# Smart_Agriculture_Schematic.net
KiCad netlist of a schematic drawn in Altium Designer
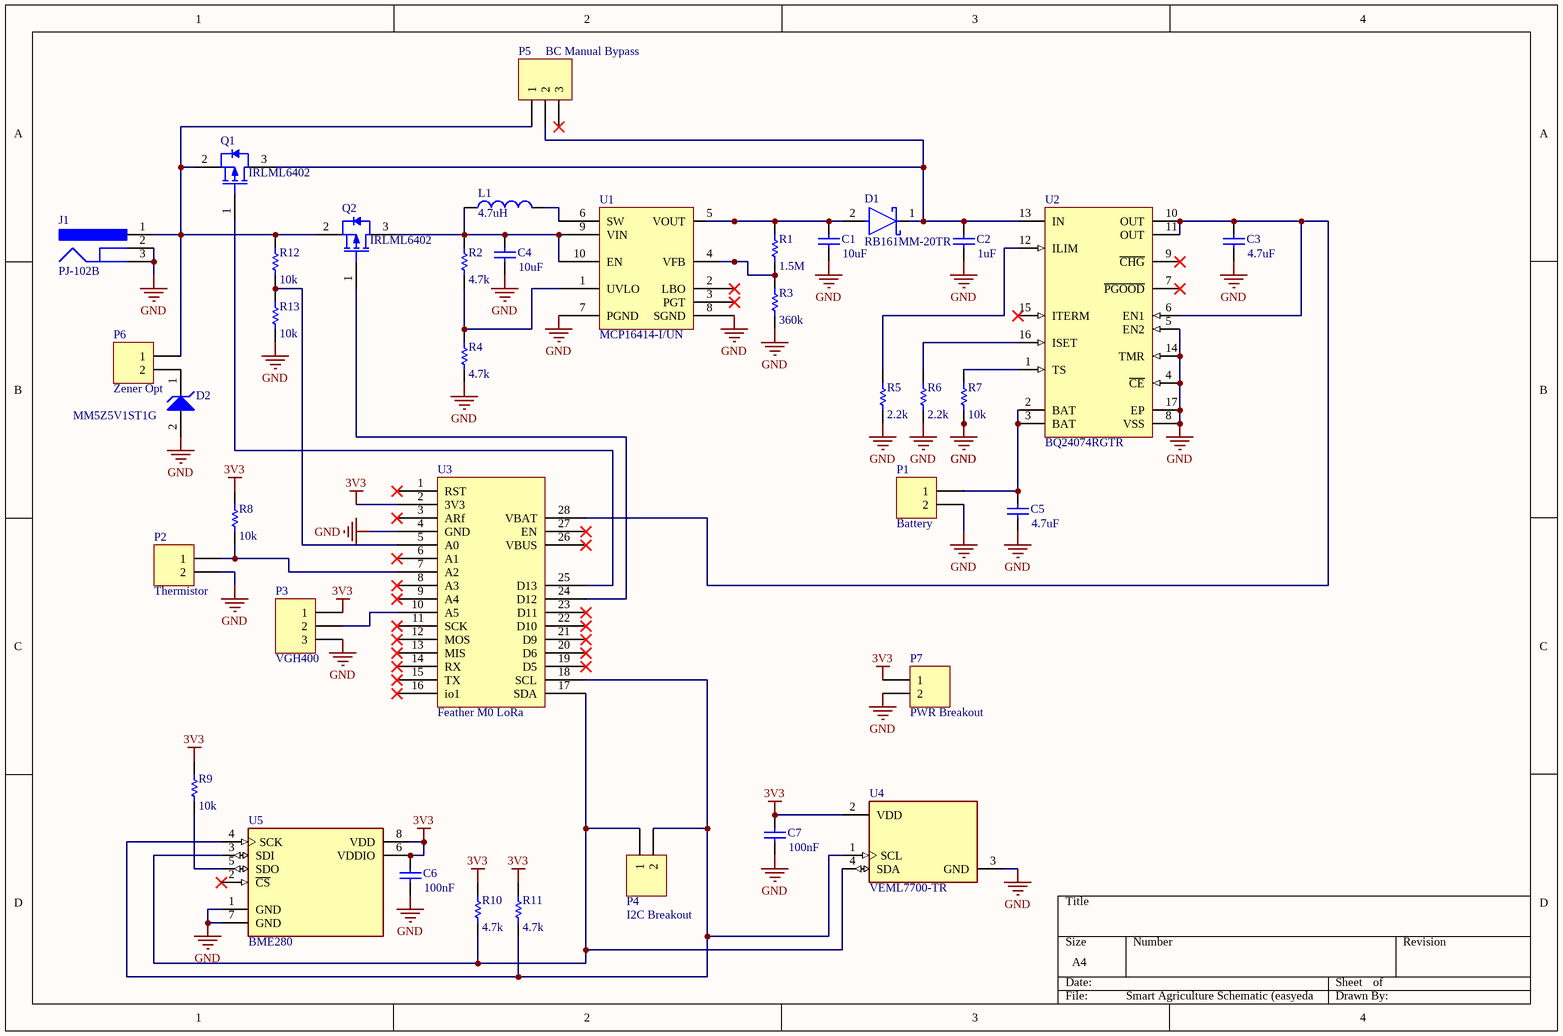
[diagram p0: Smart Agriculture Schematic (easyeda backup).SchDoc]

(export (version "E")
  (design (tool "Eeschema 10.0.6"))
  (components
    (comp (ref "C1")
      (value "10uF")
      (footprint "1608[0603]")
      (description "Capacitor")
      (fields (field (name "PUBLISHER") "Altium Limited"))
      (libsource (lib "Miscellaneous Devices") (part "Cap"))
    )
    (comp (ref "C2")
      (value "1uF")
      (footprint "1608[0603]")
      (description "Capacitor")
      (fields (field (name "PUBLISHER") "Altium Limited"))
      (libsource (lib "Miscellaneous Devices") (part "Cap"))
    )
    (comp (ref "C3")
      (value "4.7uF")
      (footprint "1608[0603]")
      (description "Capacitor")
      (fields (field (name "PUBLISHER") "Altium Limited"))
      (libsource (lib "Miscellaneous Devices") (part "Cap"))
    )
    (comp (ref "C4")
      (value "10uF")
      (footprint "1608[0603]")
      (description "Capacitor")
      (fields (field (name "PUBLISHER") "Altium Limited"))
      (libsource (lib "Miscellaneous Devices") (part "Cap"))
    )
    (comp (ref "C5")
      (value "4.7uF")
      (footprint "1608[0603]")
      (description "Capacitor")
      (fields (field (name "PUBLISHER") "Altium Limited"))
      (libsource (lib "Miscellaneous Devices") (part "Cap"))
    )
    (comp (ref "C6")
      (value "100nF")
      (footprint "1608[0603]")
      (description "Capacitor")
      (fields (field (name "PUBLISHER") "Altium Limited"))
      (libsource (lib "Miscellaneous Devices") (part "Cap"))
    )
    (comp (ref "C7")
      (value "100nF")
      (footprint "1608[0603]")
      (description "Capacitor")
      (fields (field (name "PUBLISHER") "Altium Limited"))
      (libsource (lib "Miscellaneous Devices") (part "Cap"))
    )
    (comp (ref "D1")
      (value "RB161MM-20TR")
      (footprint "FP-PMDU-MFG")
      (description "DIODE SCHOTTKY 25V 1A PMDU")
      (fields
        (field (name "MANUFACTURER") "Rohm")
        (field (name "OCTOPART") "https://octopart.com/rb161mm-20tr-rohm-50255147")
      )
      (libsource (lib "Altium Content Vault") (part "1d6ec82d83fb6aee721767c19dac4b9"))
    )
    (comp (ref "D2")
      (value "MM5Z5V1ST1G")
      (footprint "ONSC-SOD-523-2-502-01_V")
      (description "Zener Voltage Regulator, 500 mW, 2-Pin SOD-523, Pb-Free, Tape and Reel")
      (fields (field (name "MANUFACTURER") "On Semiconductor"))
      (libsource (lib "Altium Content Vault") (part "ONSC-K1A2-2"))
    )
    (comp (ref "J1")
      (value "PJ-102B")
      (footprint "CUI-PJ-102B_V")
      (fields (field (name "MANUFACTURER") "CUIInc."))
      (libsource (lib "Altium Content Vault") (part "JACK-2CD3-RN"))
    )
    (comp (ref "L1")
      (value "4.7uH")
      (footprint "1812")
      (description "Inductor")
      (fields (field (name "PUBLISHER") "Altium Limited"))
      (libsource (lib "Miscellaneous Devices") (part "Inductor"))
    )
    (comp (ref "P1")
      (value "Battery")
      (footprint "HDR1X2")
      (description "Header, 2-Pin")
      (fields (field (name "PUBLISHER") "Altium Limited"))
      (libsource (lib "") (part "Header 2_2"))
    )
    (comp (ref "P2")
      (value "Thermistor")
      (footprint "HDR1X2")
      (description "Header, 2-Pin")
      (fields (field (name "PUBLISHER") "Altium Limited"))
      (libsource (lib "") (part "Header 2_2"))
    )
    (comp (ref "P3")
      (value "VGH400")
      (footprint "HDR1X3")
      (description "Header, 3-Pin")
      (fields (field (name "PUBLISHER") "Altium Limited"))
      (libsource (lib "") (part "Header 3_1"))
    )
    (comp (ref "P4")
      (value "I2C Breakout")
      (footprint "HDR1X2")
      (description "Header, 2-Pin")
      (fields (field (name "PUBLISHER") "Altium Limited"))
      (libsource (lib "") (part "Header 2_1"))
    )
    (comp (ref "P5")
      (value "BC Manual Bypass")
      (footprint "HDR1X3")
      (description "Header, 3-Pin")
      (fields (field (name "PUBLISHER") "Altium Limited"))
      (libsource (lib "Miscellaneous Connectors") (part "Header 3"))
    )
    (comp (ref "P6")
      (value "Zener Opt")
      (footprint "HDR1X2")
      (description "Header, 2-Pin")
      (fields (field (name "PUBLISHER") "Altium Limited"))
      (libsource (lib "") (part "Header 2_2"))
    )
    (comp (ref "P7")
      (value "PWR Breakout")
      (footprint "HDR1X2")
      (description "Header, 2-Pin")
      (fields (field (name "PUBLISHER") "Altium Limited"))
      (libsource (lib "Miscellaneous Connectors") (part "Header 2"))
    )
    (comp (ref "Q1")
      (value "IRLML6402")
      (footprint "INTR-SOT-23-3_V")
      (fields (field (name "MANUFACTURER") "International Rectifier"))
      (libsource (lib "Altium Content Vault") (part "PEMOS-GSD-3"))
    )
    (comp (ref "Q2")
      (value "IRLML6402")
      (footprint "INTR-SOT-23-3_V")
      (fields (field (name "MANUFACTURER") "International Rectifier"))
      (libsource (lib "Altium Content Vault") (part "PEMOS-GSD-3"))
    )
    (comp (ref "R1")
      (value "1.5M")
      (footprint "1608[0603]")
      (description "Resistor")
      (fields (field (name "PUBLISHER") "Altium Limited"))
      (libsource (lib "Miscellaneous Devices") (part "Res1"))
    )
    (comp (ref "R2")
      (value "4.7k")
      (footprint "1608[0603]")
      (description "Resistor")
      (fields (field (name "PUBLISHER") "Altium Limited"))
      (libsource (lib "Miscellaneous Devices") (part "Res1"))
    )
    (comp (ref "R3")
      (value "360k")
      (footprint "1608[0603]")
      (description "Resistor")
      (fields (field (name "PUBLISHER") "Altium Limited"))
      (libsource (lib "Miscellaneous Devices") (part "Res1"))
    )
    (comp (ref "R4")
      (value "4.7k")
      (footprint "1608[0603]")
      (description "Resistor")
      (fields (field (name "PUBLISHER") "Altium Limited"))
      (libsource (lib "Miscellaneous Devices") (part "Res1"))
    )
    (comp (ref "R5")
      (value "2.2k")
      (footprint "1608[0603]")
      (description "Resistor")
      (fields (field (name "PUBLISHER") "Altium Limited"))
      (libsource (lib "Miscellaneous Devices") (part "Res1"))
    )
    (comp (ref "R6")
      (value "2.2k")
      (footprint "1608[0603]")
      (description "Resistor")
      (fields (field (name "PUBLISHER") "Altium Limited"))
      (libsource (lib "Miscellaneous Devices") (part "Res1"))
    )
    (comp (ref "R7")
      (value "10k")
      (footprint "1608[0603]")
      (description "Resistor")
      (fields (field (name "PUBLISHER") "Altium Limited"))
      (libsource (lib "Miscellaneous Devices") (part "Res1"))
    )
    (comp (ref "R8")
      (value "10k")
      (footprint "1608[0603]")
      (description "Resistor")
      (fields (field (name "PUBLISHER") "Altium Limited"))
      (libsource (lib "Miscellaneous Devices") (part "Res1"))
    )
    (comp (ref "R9")
      (value "10k")
      (footprint "1608[0603]")
      (description "Resistor")
      (fields (field (name "PUBLISHER") "Altium Limited"))
      (libsource (lib "Miscellaneous Devices") (part "Res1"))
    )
    (comp (ref "R10")
      (value "4.7k")
      (footprint "1608[0603]")
      (description "Resistor")
      (fields (field (name "PUBLISHER") "Altium Limited"))
      (libsource (lib "Miscellaneous Devices") (part "Res1"))
    )
    (comp (ref "R11")
      (value "4.7k")
      (footprint "1608[0603]")
      (description "Resistor")
      (fields (field (name "PUBLISHER") "Altium Limited"))
      (libsource (lib "Miscellaneous Devices") (part "Res1"))
    )
    (comp (ref "R12")
      (value "10k")
      (footprint "1608[0603]")
      (description "Resistor")
      (fields (field (name "Comment") "Res1") (field (name "PUBLISHER") "Altium Limited"))
      (libsource (lib "Miscellaneous Devices") (part "Res1"))
    )
    (comp (ref "R13")
      (value "10k")
      (footprint "1608[0603]")
      (description "Resistor")
      (fields (field (name "Comment") "Res1") (field (name "PUBLISHER") "Altium Limited"))
      (libsource (lib "Miscellaneous Devices") (part "Res1"))
    )
    (comp (ref "U1")
      (value "MCP16414-I/UN")
      (footprint "MSOP10_UN_MCH")
      (libsource (lib "MCP16414-IUN") (part "Component_1"))
    )
    (comp (ref "U2")
      (value "BQ24074RGTR")
      (footprint "RGT0016C_V")
      (fields (field (name "MANUFACTURER") "Texas Instruments"))
      (libsource (lib "Altium Content Vault") (part "TI-BQ24074RGT16-1700X1700TP"))
    )
    (comp (ref "U3")
      (value "Feather M0 LoRa")
      (footprint "FeatherM0LoRa")
      (libsource (lib "FeatherM0LoRa") (part "Feather M0 LoRa"))
    )
    (comp (ref "U4")
      (value "VEML7700-TR")
      (footprint "FP-6_550-5300_02-4-MFG")
      (description "SENSOR OPT 545NM AMBIENT 4SMD")
      (fields
        (field (name "OCTOPART") "https://octopart.com/veml7700-tr-vishay-70519713")
        (field (name "MANUFACTURER") "Vishay")
      )
      (libsource (lib "Altium Content Vault") (part "910e2da346148eee15a6bcb182505dc"))
    )
    (comp (ref "U5")
      (value "BME280")
      (footprint "FP-BME280-MFG")
      (description "SENSOR PRESSURE HUMIDITY TEMP")
      (libsource (lib "Altium Content Vault") (part "d58e2f6669bc67e6a2bc6a28610ca79"))
    )
  )
  (nets
    (net (code "1") (name "3V3") (class "Default")
      (node (ref "C6") (pin "2") (pinfunction "2_2") (pintype "passive"))
      (node (ref "C7") (pin "2") (pinfunction "2_2") (pintype "passive"))
      (node (ref "P3") (pin "1") (pinfunction "1_1") (pintype "passive"))
      (node (ref "P7") (pin "1") (pinfunction "1_1") (pintype "passive"))
      (node (ref "R10") (pin "2") (pinfunction "2_2") (pintype "passive"))
      (node (ref "R11") (pin "2") (pinfunction "2_2") (pintype "passive"))
      (node (ref "R8") (pin "2") (pinfunction "2_2") (pintype "passive"))
      (node (ref "R9") (pin "2") (pinfunction "2_2") (pintype "passive"))
      (node (ref "U3") (pin "2") (pinfunction "3V3_2") (pintype "passive"))
      (node (ref "U4") (pin "2") (pinfunction "VDD_2") (pintype "power_in"))
      (node (ref "U5") (pin "6") (pinfunction "VDDIO_6") (pintype "power_in"))
      (node (ref "U5") (pin "8") (pinfunction "VDD_8") (pintype "power_in"))
    )
    (net (code "2") (name "GND") (class "Default")
      (node (ref "C1") (pin "1") (pinfunction "1_1") (pintype "passive"))
      (node (ref "C2") (pin "1") (pinfunction "1_1") (pintype "passive"))
      (node (ref "C3") (pin "1") (pinfunction "1_1") (pintype "passive"))
      (node (ref "C4") (pin "1") (pinfunction "1_1") (pintype "passive"))
      (node (ref "C5") (pin "1") (pinfunction "1_1") (pintype "passive"))
      (node (ref "C6") (pin "1") (pinfunction "1_1") (pintype "passive"))
      (node (ref "C7") (pin "1") (pinfunction "1_1") (pintype "passive"))
      (node (ref "D2") (pin "2") (pinfunction "A_2") (pintype "passive"))
      (node (ref "J1") (pin "2") (pinfunction "2_2") (pintype "passive"))
      (node (ref "J1") (pin "3") (pinfunction "3_3") (pintype "passive"))
      (node (ref "P1") (pin "2") (pinfunction "2_2") (pintype "passive"))
      (node (ref "P2") (pin "2") (pinfunction "2_2") (pintype "passive"))
      (node (ref "P3") (pin "3") (pinfunction "3_3") (pintype "passive"))
      (node (ref "P7") (pin "2") (pinfunction "2_2") (pintype "passive"))
      (node (ref "R13") (pin "1") (pinfunction "1_1") (pintype "passive"))
      (node (ref "R3") (pin "1") (pinfunction "1_1") (pintype "passive"))
      (node (ref "R4") (pin "1") (pinfunction "1_1") (pintype "passive"))
      (node (ref "R5") (pin "1") (pinfunction "1_1") (pintype "passive"))
      (node (ref "R6") (pin "1") (pinfunction "1_1") (pintype "passive"))
      (node (ref "R7") (pin "1") (pinfunction "1_1") (pintype "passive"))
      (node (ref "U1") (pin "7") (pinfunction "PGND_7") (pintype "passive"))
      (node (ref "U1") (pin "8") (pinfunction "SGND_8") (pintype "passive"))
      (node (ref "U2") (pin "14") (pinfunction "TMR_14") (pintype "input"))
      (node (ref "U2") (pin "17") (pinfunction "EP_17") (pintype "power_in"))
      (node (ref "U2") (pin "4") (pinfunction "~{CE}_4") (pintype "input"))
      (node (ref "U2") (pin "5") (pinfunction "EN2_5") (pintype "input"))
      (node (ref "U2") (pin "8") (pinfunction "VSS_8") (pintype "power_in"))
      (node (ref "U3") (pin "4") (pinfunction "GND_4") (pintype "passive"))
      (node (ref "U4") (pin "3") (pinfunction "GND_3") (pintype "power_in"))
      (node (ref "U5") (pin "1") (pinfunction "GND_1") (pintype "power_in"))
      (node (ref "U5") (pin "7") (pinfunction "GND_7") (pintype "power_in"))
    )
    (net (code "3") (name "Net-(C5-Pad2)") (class "Default")
      (node (ref "C5") (pin "2") (pinfunction "2_2") (pintype "passive"))
      (node (ref "P1") (pin "1") (pinfunction "1_1") (pintype "passive"))
      (node (ref "U2") (pin "2") (pinfunction "BAT_2") (pintype "power_in"))
      (node (ref "U2") (pin "3") (pinfunction "BAT_3") (pintype "power_in"))
    )
    (net (code "4") (name "Net-(D1-A)") (class "Default")
      (node (ref "C1") (pin "2") (pinfunction "2_2") (pintype "passive"))
      (node (ref "D1") (pin "2") (pinfunction "A_2") (pintype "passive"))
      (node (ref "R1") (pin "2") (pinfunction "2_2") (pintype "passive"))
      (node (ref "U1") (pin "5") (pinfunction "VOUT_5") (pintype "passive"))
    )
    (net (code "5") (name "Net-(D1-C)") (class "Default")
      (node (ref "C2") (pin "2") (pinfunction "2_2") (pintype "passive"))
      (node (ref "D1") (pin "1") (pinfunction "C_1") (pintype "passive"))
      (node (ref "P5") (pin "2") (pinfunction "2_2") (pintype "passive"))
      (node (ref "Q1") (pin "3") (pinfunction "DRAIN_3") (pintype "passive"))
      (node (ref "U2") (pin "13") (pinfunction "IN_13") (pintype "power_in"))
    )
    (net (code "6") (name "Net-(D2-K)") (class "Default")
      (node (ref "D2") (pin "1") (pinfunction "K_1") (pintype "passive"))
      (node (ref "P6") (pin "2") (pinfunction "2_2") (pintype "passive"))
    )
    (net (code "7") (name "Net-(Q1-GATE)") (class "Default")
      (node (ref "Q1") (pin "1") (pinfunction "GATE_1") (pintype "passive"))
      (node (ref "U3") (pin "25") (pinfunction "D13_25") (pintype "passive"))
    )
    (net (code "8") (name "Net-(Q1-SOURCE)") (class "Default")
      (node (ref "J1") (pin "1") (pinfunction "1_1") (pintype "passive"))
      (node (ref "P5") (pin "1") (pinfunction "1_1") (pintype "passive"))
      (node (ref "P6") (pin "1") (pinfunction "1_1") (pintype "passive"))
      (node (ref "Q1") (pin "2") (pinfunction "SOURCE_2") (pintype "passive"))
      (node (ref "Q2") (pin "2") (pinfunction "SOURCE_2") (pintype "passive"))
      (node (ref "R12") (pin "2") (pinfunction "2_2") (pintype "passive"))
    )
    (net (code "9") (name "Net-(Q2-DRAIN)") (class "Default")
      (node (ref "C4") (pin "2") (pinfunction "2_2") (pintype "passive"))
      (node (ref "L1") (pin "1") (pinfunction "1_1") (pintype "passive"))
      (node (ref "Q2") (pin "3") (pinfunction "DRAIN_3") (pintype "passive"))
      (node (ref "R2") (pin "2") (pinfunction "2_2") (pintype "passive"))
      (node (ref "U1") (pin "10") (pinfunction "EN_10") (pintype "passive"))
      (node (ref "U1") (pin "9") (pinfunction "VIN_9") (pintype "passive"))
    )
    (net (code "10") (name "Net-(Q2-GATE)") (class "Default")
      (node (ref "Q2") (pin "1") (pinfunction "GATE_1") (pintype "passive"))
      (node (ref "U3") (pin "24") (pinfunction "D12_24") (pintype "passive"))
    )
    (net (code "11") (name "Net-(U1-SW)") (class "Default")
      (node (ref "L1") (pin "2") (pinfunction "2_2") (pintype "passive"))
      (node (ref "U1") (pin "6") (pinfunction "SW_6") (pintype "passive"))
    )
    (net (code "12") (name "Net-(U1-UVLO)") (class "Default")
      (node (ref "R2") (pin "1") (pinfunction "1_1") (pintype "passive"))
      (node (ref "R4") (pin "2") (pinfunction "2_2") (pintype "passive"))
      (node (ref "U1") (pin "1") (pinfunction "UVLO_1") (pintype "passive"))
    )
    (net (code "13") (name "Net-(U1-VFB)") (class "Default")
      (node (ref "R1") (pin "1") (pinfunction "1_1") (pintype "passive"))
      (node (ref "R3") (pin "2") (pinfunction "2_2") (pintype "passive"))
      (node (ref "U1") (pin "4") (pinfunction "VFB_4") (pintype "passive"))
    )
    (net (code "14") (name "Net-(U2-EN1)") (class "Default")
      (node (ref "C3") (pin "2") (pinfunction "2_2") (pintype "passive"))
      (node (ref "U2") (pin "10") (pinfunction "OUT_10") (pintype "power_in"))
      (node (ref "U2") (pin "11") (pinfunction "OUT_11") (pintype "power_in"))
      (node (ref "U2") (pin "6") (pinfunction "EN1_6") (pintype "input"))
      (node (ref "U3") (pin "28") (pinfunction "VBAT_28") (pintype "passive"))
    )
    (net (code "15") (name "Net-(U2-ILIM)") (class "Default")
      (node (ref "R5") (pin "2") (pinfunction "2_2") (pintype "passive"))
      (node (ref "U2") (pin "12") (pinfunction "ILIM_12") (pintype "input"))
    )
    (net (code "16") (name "Net-(U2-ISET)") (class "Default")
      (node (ref "R6") (pin "2") (pinfunction "2_2") (pintype "passive"))
      (node (ref "U2") (pin "16") (pinfunction "ISET_16") (pintype "input"))
    )
    (net (code "17") (name "Net-(U2-TS)") (class "Default")
      (node (ref "R7") (pin "2") (pinfunction "2_2") (pintype "passive"))
      (node (ref "U2") (pin "1") (pinfunction "TS_1") (pintype "input"))
    )
    (net (code "18") (name "Net-(U3-A0)") (class "Default")
      (node (ref "R12") (pin "1") (pinfunction "1_1") (pintype "passive"))
      (node (ref "R13") (pin "2") (pinfunction "2_2") (pintype "passive"))
      (node (ref "U3") (pin "5") (pinfunction "A0_5") (pintype "passive"))
    )
    (net (code "19") (name "Net-(U3-A2)") (class "Default")
      (node (ref "P2") (pin "1") (pinfunction "1_1") (pintype "passive"))
      (node (ref "R8") (pin "1") (pinfunction "1_1") (pintype "passive"))
      (node (ref "U3") (pin "7") (pinfunction "A2_7") (pintype "passive"))
    )
    (net (code "20") (name "Net-(U3-A5)") (class "Default")
      (node (ref "P3") (pin "2") (pinfunction "2_2") (pintype "passive"))
      (node (ref "U3") (pin "10") (pinfunction "A5_10") (pintype "passive"))
    )
    (net (code "21") (name "Net-(U3-SCL)") (class "Default")
      (node (ref "P4") (pin "2") (pinfunction "2_2") (pintype "passive"))
      (node (ref "R11") (pin "1") (pinfunction "1_1") (pintype "passive"))
      (node (ref "U3") (pin "18") (pinfunction "SCL_18") (pintype "passive"))
      (node (ref "U4") (pin "1") (pinfunction "SCL_1") (pintype "input"))
      (node (ref "U5") (pin "4") (pinfunction "SCK_4") (pintype "input"))
    )
    (net (code "22") (name "Net-(U3-SDA)") (class "Default")
      (node (ref "P4") (pin "1") (pinfunction "1_1") (pintype "passive"))
      (node (ref "R10") (pin "1") (pinfunction "1_1") (pintype "passive"))
      (node (ref "U3") (pin "17") (pinfunction "SDA_17") (pintype "passive"))
      (node (ref "U4") (pin "4") (pinfunction "SDA_4") (pintype "bidirectional"))
      (node (ref "U5") (pin "3") (pinfunction "SDI_3") (pintype "bidirectional"))
    )
    (net (code "23") (name "Net-(U5-SDO)") (class "Default")
      (node (ref "R9") (pin "1") (pinfunction "1_1") (pintype "passive"))
      (node (ref "U5") (pin "5") (pinfunction "SDO_5") (pintype "bidirectional"))
    )
    (net (code "24") (name "unconnected-(P5-Pad3)") (class "Default")
      (node (ref "P5") (pin "3") (pinfunction "3_3") (pintype "passive+no_connect"))
    )
    (net (code "25") (name "unconnected-(U1-LBO-Pad2)") (class "Default")
      (node (ref "U1") (pin "2") (pinfunction "LBO_2") (pintype "passive+no_connect"))
    )
    (net (code "26") (name "unconnected-(U1-PGT-Pad3)") (class "Default")
      (node (ref "U1") (pin "3") (pinfunction "PGT_3") (pintype "passive+no_connect"))
    )
    (net (code "27") (name "unconnected-(U2-ITERM-Pad15)") (class "Default")
      (node (ref "U2") (pin "15") (pinfunction "ITERM_15") (pintype "input+no_connect"))
    )
    (net (code "28") (name "unconnected-(U2-~{CHG}-Pad9)") (class "Default")
      (node (ref "U2") (pin "9") (pinfunction "~{CHG}_9") (pintype "tri_state+no_connect"))
    )
    (net (code "29") (name "unconnected-(U2-~{PGOOD}-Pad7)") (class "Default")
      (node (ref "U2") (pin "7") (pinfunction "~{PGOOD}_7") (pintype "tri_state+no_connect"))
    )
    (net (code "30") (name "unconnected-(U3-A1-Pad6)") (class "Default")
      (node (ref "U3") (pin "6") (pinfunction "A1_6") (pintype "passive+no_connect"))
    )
    (net (code "31") (name "unconnected-(U3-A3-Pad8)") (class "Default")
      (node (ref "U3") (pin "8") (pinfunction "A3_8") (pintype "passive+no_connect"))
    )
    (net (code "32") (name "unconnected-(U3-A4-Pad9)") (class "Default")
      (node (ref "U3") (pin "9") (pinfunction "A4_9") (pintype "passive+no_connect"))
    )
    (net (code "33") (name "unconnected-(U3-ARf-Pad3)") (class "Default")
      (node (ref "U3") (pin "3") (pinfunction "ARf_3") (pintype "passive+no_connect"))
    )
    (net (code "34") (name "unconnected-(U3-D5-Pad19)") (class "Default")
      (node (ref "U3") (pin "19") (pinfunction "D5_19") (pintype "passive+no_connect"))
    )
    (net (code "35") (name "unconnected-(U3-D6-Pad20)") (class "Default")
      (node (ref "U3") (pin "20") (pinfunction "D6_20") (pintype "passive+no_connect"))
    )
    (net (code "36") (name "unconnected-(U3-D9-Pad21)") (class "Default")
      (node (ref "U3") (pin "21") (pinfunction "D9_21") (pintype "passive+no_connect"))
    )
    (net (code "37") (name "unconnected-(U3-D10-Pad22)") (class "Default")
      (node (ref "U3") (pin "22") (pinfunction "D10_22") (pintype "passive+no_connect"))
    )
    (net (code "38") (name "unconnected-(U3-D11-Pad23)") (class "Default")
      (node (ref "U3") (pin "23") (pinfunction "D11_23") (pintype "passive+no_connect"))
    )
    (net (code "39") (name "unconnected-(U3-EN-Pad27)") (class "Default")
      (node (ref "U3") (pin "27") (pinfunction "EN_27") (pintype "passive+no_connect"))
    )
    (net (code "40") (name "unconnected-(U3-MIS-Pad13)") (class "Default")
      (node (ref "U3") (pin "13") (pinfunction "MIS_13") (pintype "passive+no_connect"))
    )
    (net (code "41") (name "unconnected-(U3-MOS-Pad12)") (class "Default")
      (node (ref "U3") (pin "12") (pinfunction "MOS_12") (pintype "passive+no_connect"))
    )
    (net (code "42") (name "unconnected-(U3-RST-Pad1)") (class "Default")
      (node (ref "U3") (pin "1") (pinfunction "RST_1") (pintype "passive+no_connect"))
    )
    (net (code "43") (name "unconnected-(U3-RX-Pad14)") (class "Default")
      (node (ref "U3") (pin "14") (pinfunction "RX_14") (pintype "passive+no_connect"))
    )
    (net (code "44") (name "unconnected-(U3-SCK-Pad11)") (class "Default")
      (node (ref "U3") (pin "11") (pinfunction "SCK_11") (pintype "passive+no_connect"))
    )
    (net (code "45") (name "unconnected-(U3-TX-Pad15)") (class "Default")
      (node (ref "U3") (pin "15") (pinfunction "TX_15") (pintype "passive+no_connect"))
    )
    (net (code "46") (name "unconnected-(U3-VBUS-Pad26)") (class "Default")
      (node (ref "U3") (pin "26") (pinfunction "VBUS_26") (pintype "passive+no_connect"))
    )
    (net (code "47") (name "unconnected-(U3-io1-Pad16)") (class "Default")
      (node (ref "U3") (pin "16") (pinfunction "io1_16") (pintype "passive+no_connect"))
    )
    (net (code "48") (name "unconnected-(U5-~{CS}-Pad2)") (class "Default")
      (node (ref "U5") (pin "2") (pinfunction "~{CS}_2") (pintype "input+no_connect"))
    )
  )
)
